# LoRa_SX1276_Shield_-_v1_1_0.net
KiCad netlist of a schematic drawn in EAGLE
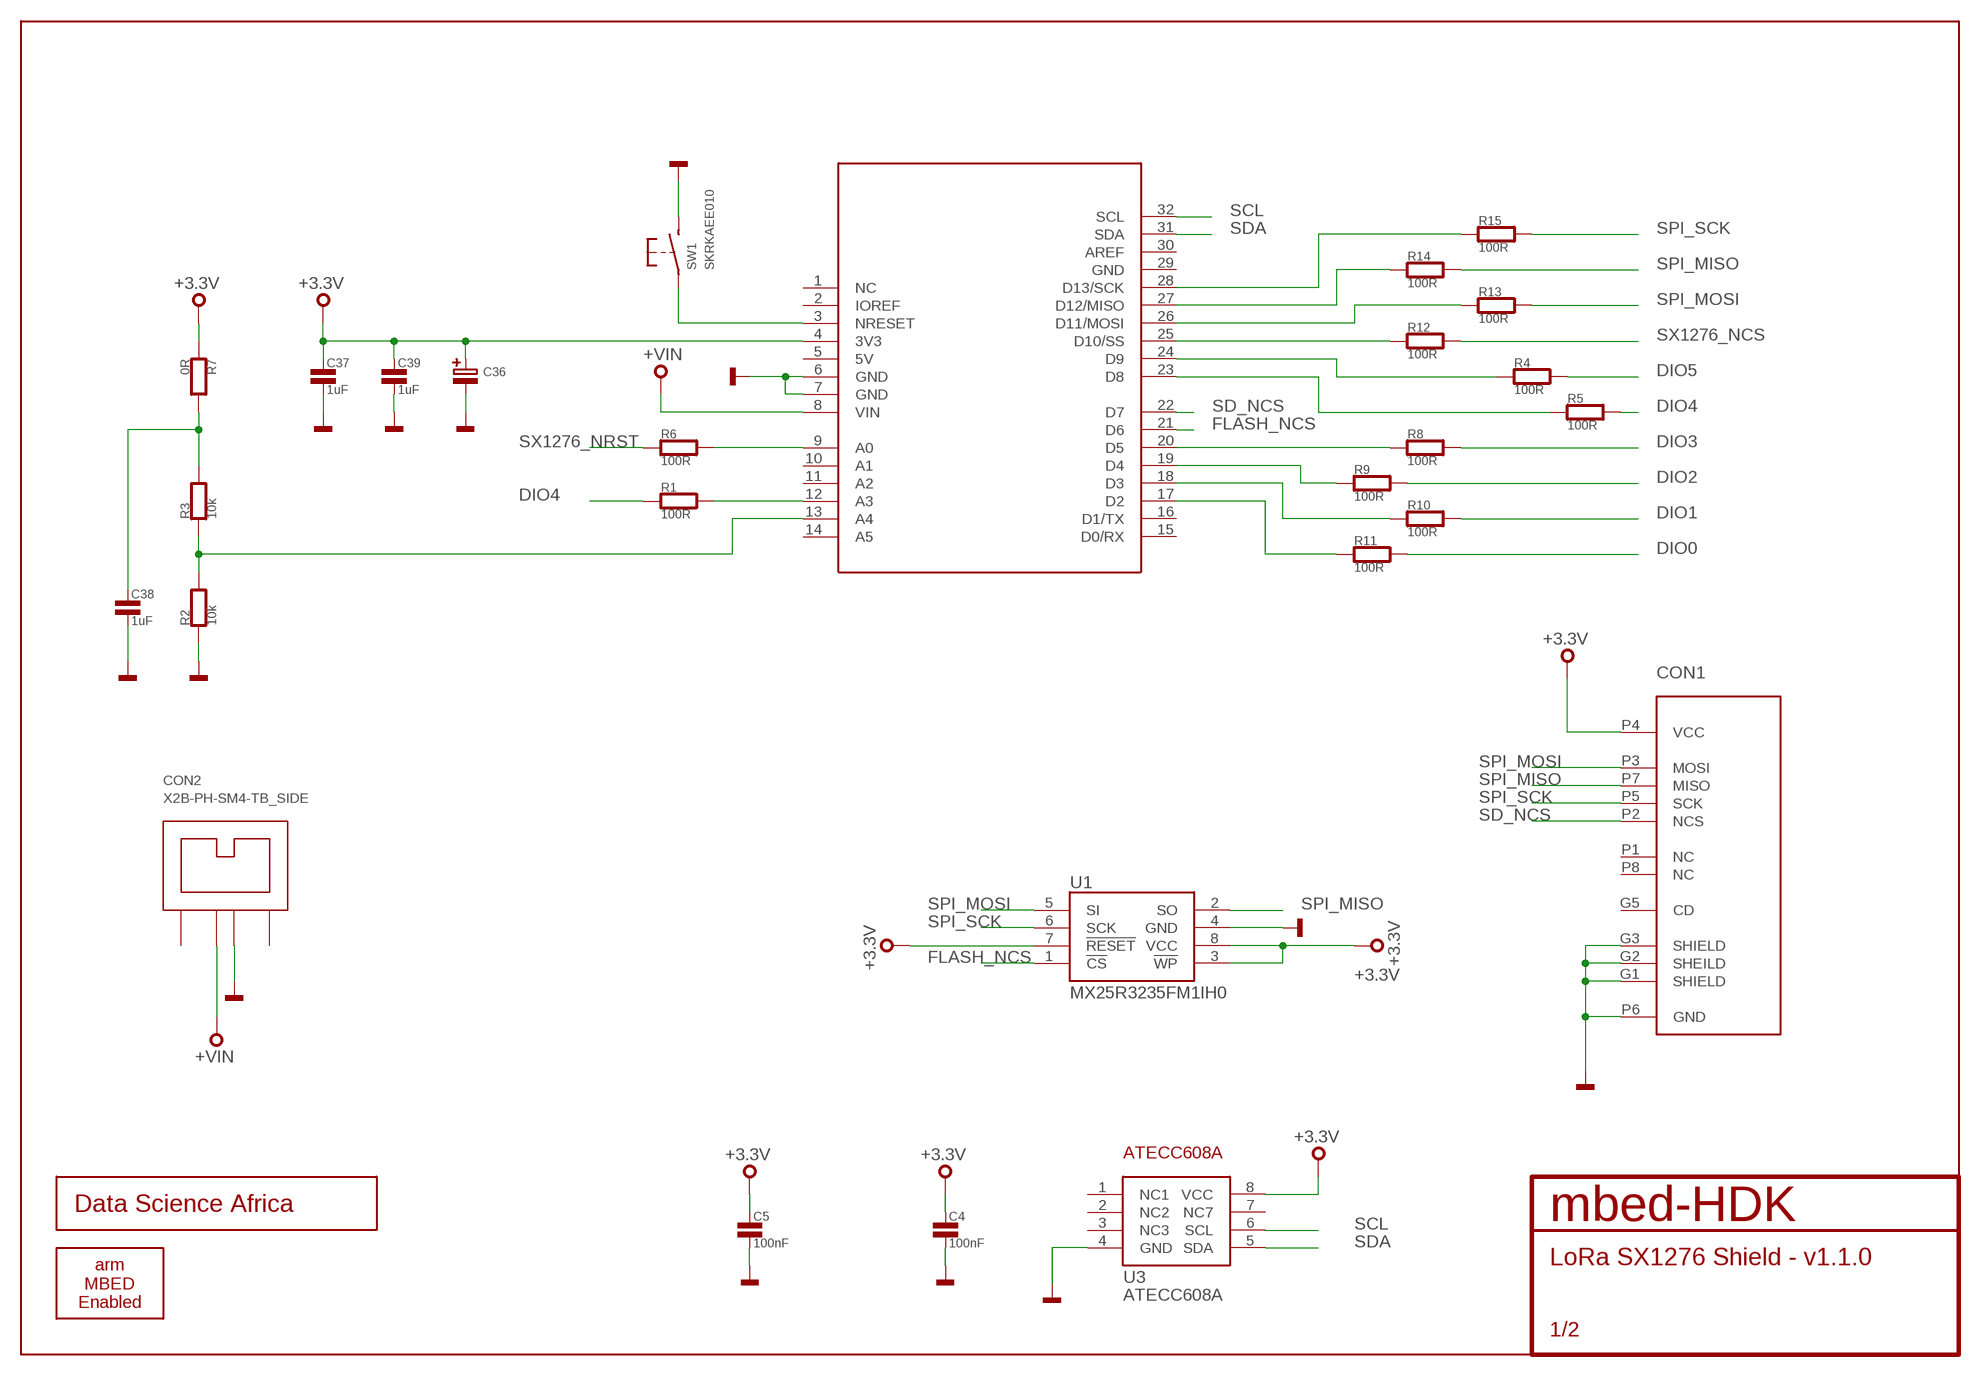
[diagram p0: schematic, sheet 1]
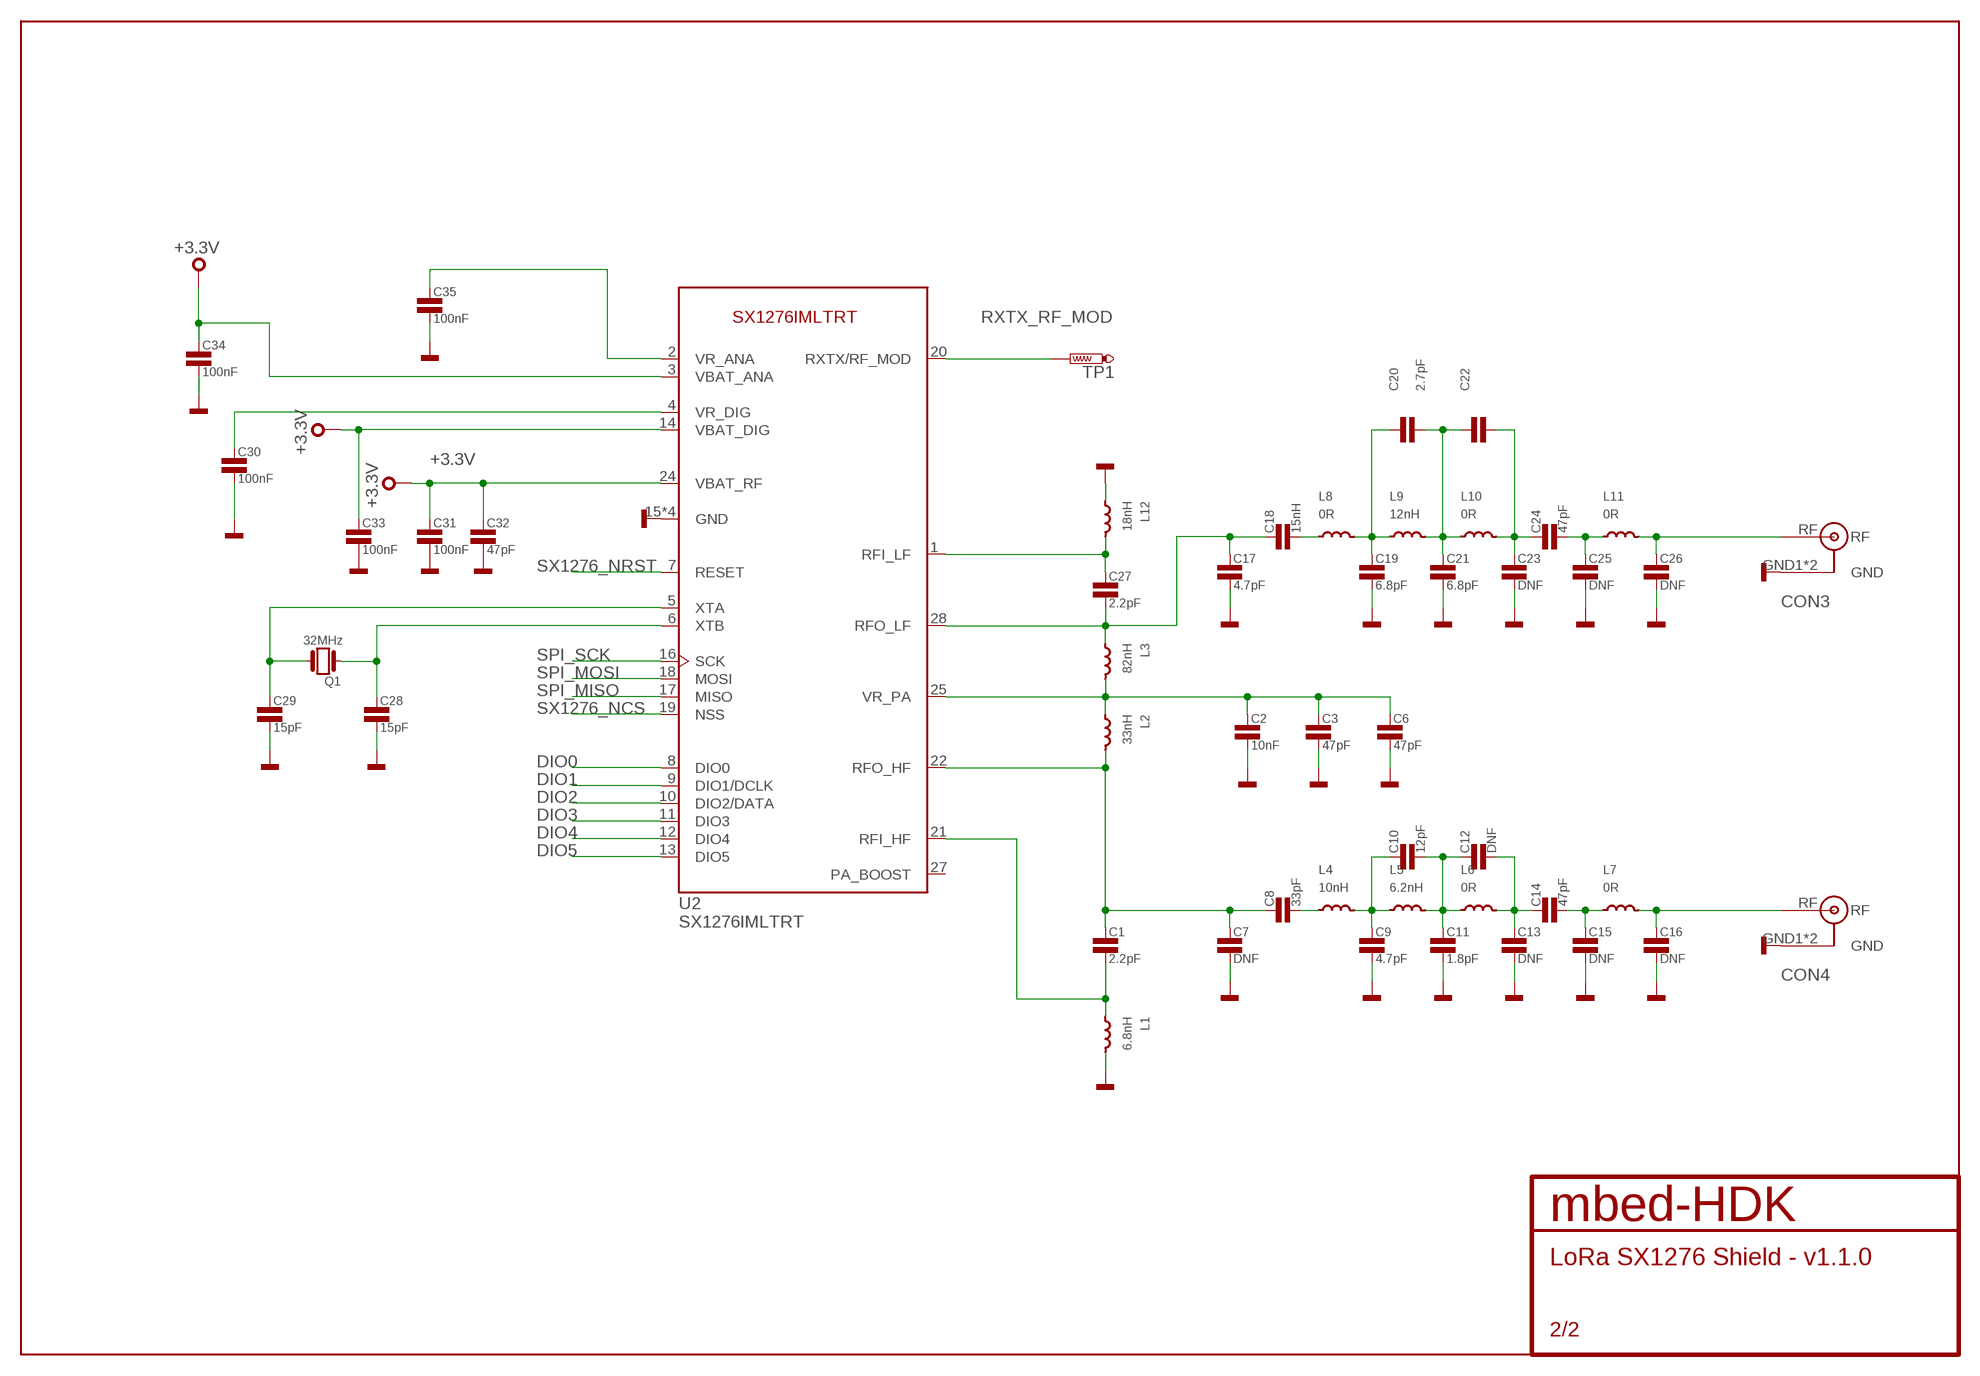
[diagram p1: schematic, sheet 2]

(export (version "E")
  (design (tool "Eeschema 10.0.6"))
  (components
    (comp (ref "C1")
      (value "2.2pF")
      (footprint "eagle-import:0402")
      (libsource (lib "eagle-import") (part "C0402"))
    )
    (comp (ref "C2")
      (value "10nF")
      (footprint "eagle-import:0402")
      (libsource (lib "eagle-import") (part "C0402"))
    )
    (comp (ref "C3")
      (value "47pF")
      (footprint "eagle-import:0402")
      (libsource (lib "eagle-import") (part "C0402"))
    )
    (comp (ref "C6")
      (value "47pF")
      (footprint "eagle-import:0402")
      (libsource (lib "eagle-import") (part "C0402"))
    )
    (comp (ref "C7")
      (value "DNF")
      (footprint "eagle-import:0402")
      (libsource (lib "eagle-import") (part "C0402"))
    )
    (comp (ref "C8")
      (value "33pF")
      (footprint "eagle-import:0402")
      (libsource (lib "eagle-import") (part "C0402"))
    )
    (comp (ref "C9")
      (value "4.7pF")
      (footprint "eagle-import:0402")
      (libsource (lib "eagle-import") (part "C0402"))
    )
    (comp (ref "C10")
      (value "12pF")
      (footprint "eagle-import:0402")
      (libsource (lib "eagle-import") (part "C0402"))
    )
    (comp (ref "C11")
      (value "1.8pF")
      (footprint "eagle-import:0402")
      (libsource (lib "eagle-import") (part "C0402"))
    )
    (comp (ref "C12")
      (value "DNF")
      (footprint "eagle-import:0402")
      (libsource (lib "eagle-import") (part "C0402"))
    )
    (comp (ref "C13")
      (value "DNF")
      (footprint "eagle-import:0402")
      (libsource (lib "eagle-import") (part "C0402"))
    )
    (comp (ref "C14")
      (value "47pF")
      (footprint "eagle-import:0402")
      (libsource (lib "eagle-import") (part "C0402"))
    )
    (comp (ref "C15")
      (value "DNF")
      (footprint "eagle-import:0402")
      (libsource (lib "eagle-import") (part "C0402"))
    )
    (comp (ref "C16")
      (value "DNF")
      (footprint "eagle-import:0402")
      (libsource (lib "eagle-import") (part "C0402"))
    )
    (comp (ref "C17")
      (value "4.7pF")
      (footprint "eagle-import:0402")
      (libsource (lib "eagle-import") (part "C0402"))
    )
    (comp (ref "C18")
      (value "15nH")
      (footprint "eagle-import:0402")
      (libsource (lib "eagle-import") (part "C0402"))
    )
    (comp (ref "C19")
      (value "6.8pF")
      (footprint "eagle-import:0402")
      (libsource (lib "eagle-import") (part "C0402"))
    )
    (comp (ref "C20")
      (value "2.7pF")
      (footprint "eagle-import:0402")
      (libsource (lib "eagle-import") (part "C0402"))
    )
    (comp (ref "C21")
      (value "6.8pF")
      (footprint "eagle-import:0402")
      (libsource (lib "eagle-import") (part "C0402"))
    )
    (comp (ref "C22")
      (value "C0402")
      (footprint "eagle-import:0402")
      (libsource (lib "eagle-import") (part "C0402"))
    )
    (comp (ref "C23")
      (value "DNF")
      (footprint "eagle-import:0402")
      (libsource (lib "eagle-import") (part "C0402"))
    )
    (comp (ref "C24")
      (value "47pF")
      (footprint "eagle-import:0402")
      (libsource (lib "eagle-import") (part "C0402"))
    )
    (comp (ref "C25")
      (value "DNF")
      (footprint "eagle-import:0402")
      (libsource (lib "eagle-import") (part "C0402"))
    )
    (comp (ref "C26")
      (value "DNF")
      (footprint "eagle-import:0402")
      (libsource (lib "eagle-import") (part "C0402"))
    )
    (comp (ref "C27")
      (value "2.2pF")
      (footprint "eagle-import:0402")
      (libsource (lib "eagle-import") (part "C0402"))
    )
    (comp (ref "C28")
      (value "15pF")
      (footprint "eagle-import:0402")
      (libsource (lib "eagle-import") (part "C0402"))
    )
    (comp (ref "C29")
      (value "15pF")
      (footprint "eagle-import:0402")
      (libsource (lib "eagle-import") (part "C0402"))
    )
    (comp (ref "C30")
      (value "100nF")
      (footprint "eagle-import:0402")
      (libsource (lib "eagle-import") (part "C0402"))
    )
    (comp (ref "C31")
      (value "100nF")
      (footprint "eagle-import:0402")
      (libsource (lib "eagle-import") (part "C0402"))
    )
    (comp (ref "C32")
      (value "47pF")
      (footprint "eagle-import:0402")
      (libsource (lib "eagle-import") (part "C0402"))
    )
    (comp (ref "C33")
      (value "100nF")
      (footprint "eagle-import:0402")
      (libsource (lib "eagle-import") (part "C0402"))
    )
    (comp (ref "C34")
      (value "100nF")
      (footprint "eagle-import:0402")
      (libsource (lib "eagle-import") (part "C0402"))
    )
    (comp (ref "C35")
      (value "100nF")
      (footprint "eagle-import:0402")
      (libsource (lib "eagle-import") (part "C0402"))
    )
    (comp (ref "CON3")
      (value "U.FL")
      (footprint "eagle-import:U.FL-R-SMT-1")
      (fields (field (name "MF") "Hirose"))
      (libsource (lib "eagle-import") (part "U.FL"))
    )
    (comp (ref "CON4")
      (value "U.FL")
      (footprint "eagle-import:U.FL-R-SMT-1")
      (fields (field (name "MF") "Hirose"))
      (libsource (lib "eagle-import") (part "U.FL"))
    )
    (comp (ref "L1")
      (value "6.8nH")
      (footprint "eagle-import:0402")
      (libsource (lib "eagle-import") (part "L0402"))
    )
    (comp (ref "L2")
      (value "33nH")
      (footprint "eagle-import:0402")
      (libsource (lib "eagle-import") (part "L0402"))
    )
    (comp (ref "L3")
      (value "82nH")
      (footprint "eagle-import:0402")
      (libsource (lib "eagle-import") (part "L0402"))
    )
    (comp (ref "L4")
      (value "10nH")
      (footprint "eagle-import:0402")
      (libsource (lib "eagle-import") (part "L0402"))
    )
    (comp (ref "L5")
      (value "6.2nH")
      (footprint "eagle-import:0402")
      (libsource (lib "eagle-import") (part "L0402"))
    )
    (comp (ref "L6")
      (value "0R")
      (footprint "eagle-import:0402")
      (libsource (lib "eagle-import") (part "L0402"))
    )
    (comp (ref "L7")
      (value "0R")
      (footprint "eagle-import:0402")
      (libsource (lib "eagle-import") (part "L0402"))
    )
    (comp (ref "L8")
      (value "0R")
      (footprint "eagle-import:0402")
      (libsource (lib "eagle-import") (part "L0402"))
    )
    (comp (ref "L9")
      (value "12nH")
      (footprint "eagle-import:0402")
      (libsource (lib "eagle-import") (part "L0402"))
    )
    (comp (ref "L10")
      (value "0R")
      (footprint "eagle-import:0402")
      (libsource (lib "eagle-import") (part "L0402"))
    )
    (comp (ref "L11")
      (value "0R")
      (footprint "eagle-import:0402")
      (libsource (lib "eagle-import") (part "L0402"))
    )
    (comp (ref "L12")
      (value "18nH")
      (footprint "eagle-import:0402")
      (libsource (lib "eagle-import") (part "L0402"))
    )
    (comp (ref "Q1")
      (value "32MHz")
      (footprint "eagle-import:3.2X.2.5")
      (libsource (lib "eagle-import") (part "GENERIC-CRYSTAL_3.2X2.5"))
    )
    (comp (ref "TP1")
      (value "PTR1TP12R")
      (footprint "eagle-import:TP12R")
      (libsource (lib "eagle-import") (part "PTR1TP12R"))
    )
    (comp (ref "U2")
      (value "SX1276IMLTRT")
      (footprint "eagle-import:QFN65P600X600X100-29N")
      (fields (field (name "MF") "Semtec"))
      (libsource (lib "eagle-import") (part "SX1276IMLTRT"))
    )
    (comp (ref "BRD2")
      (value "ARDUINO-R3_APPS")
      (footprint "eagle-import:ARDUINO-R3-APPS-SHEILD")
      (libsource (lib "eagle-import") (part "ARDUINO-R3_APPS"))
    )
    (comp (ref "C4")
      (value "100nF")
      (footprint "eagle-import:0402")
      (libsource (lib "eagle-import") (part "C0402"))
    )
    (comp (ref "C5")
      (value "100nF")
      (footprint "eagle-import:0402")
      (libsource (lib "eagle-import") (part "C0402"))
    )
    (comp (ref "C36")
      (value "C-POLB")
      (footprint "eagle-import:SMC_B")
      (fields (field (name "MF") "Kemet"))
      (libsource (lib "eagle-import") (part "C-POLB"))
    )
    (comp (ref "C37")
      (value "1uF")
      (footprint "eagle-import:0603")
      (libsource (lib "eagle-import") (part "C0603"))
    )
    (comp (ref "C38")
      (value "1uF")
      (footprint "eagle-import:0603")
      (libsource (lib "eagle-import") (part "C0603"))
    )
    (comp (ref "C39")
      (value "1uF")
      (footprint "eagle-import:0402")
      (libsource (lib "eagle-import") (part "C0402"))
    )
    (comp (ref "CON1")
      (value "MICRO-SDMOLEX-47571-0001")
      (footprint "eagle-import:MOLEX-47571-0001")
      (libsource (lib "eagle-import") (part "MICRO-SDMOLEX-47571-0001"))
    )
    (comp (ref "CON2")
      (value "X2B-PH-SM4-TB_SIDE")
      (footprint "eagle-import:S2B-PH-SM4-TB")
      (libsource (lib "eagle-import") (part "X2B-PH-SM4-TB_SIDE"))
    )
    (comp (ref "R1")
      (value "100R")
      (footprint "eagle-import:0402")
      (libsource (lib "eagle-import") (part "R0402"))
    )
    (comp (ref "R2")
      (value "10k")
      (footprint "eagle-import:0402")
      (libsource (lib "eagle-import") (part "R0402"))
    )
    (comp (ref "R3")
      (value "10k")
      (footprint "eagle-import:0402")
      (libsource (lib "eagle-import") (part "R0402"))
    )
    (comp (ref "R4")
      (value "100R")
      (footprint "eagle-import:0402")
      (libsource (lib "eagle-import") (part "R0402"))
    )
    (comp (ref "R5")
      (value "100R")
      (footprint "eagle-import:0402")
      (libsource (lib "eagle-import") (part "R0402"))
    )
    (comp (ref "R6")
      (value "100R")
      (footprint "eagle-import:0402")
      (libsource (lib "eagle-import") (part "R0402"))
    )
    (comp (ref "R7")
      (value "0R")
      (footprint "eagle-import:0402")
      (libsource (lib "eagle-import") (part "R0402"))
    )
    (comp (ref "R8")
      (value "100R")
      (footprint "eagle-import:0402")
      (libsource (lib "eagle-import") (part "R0402"))
    )
    (comp (ref "R9")
      (value "100R")
      (footprint "eagle-import:0402")
      (libsource (lib "eagle-import") (part "R0402"))
    )
    (comp (ref "R10")
      (value "100R")
      (footprint "eagle-import:0402")
      (libsource (lib "eagle-import") (part "R0402"))
    )
    (comp (ref "R11")
      (value "100R")
      (footprint "eagle-import:0402")
      (libsource (lib "eagle-import") (part "R0402"))
    )
    (comp (ref "R12")
      (value "100R")
      (footprint "eagle-import:0402")
      (libsource (lib "eagle-import") (part "R0402"))
    )
    (comp (ref "R13")
      (value "100R")
      (footprint "eagle-import:0402")
      (libsource (lib "eagle-import") (part "R0402"))
    )
    (comp (ref "R14")
      (value "100R")
      (footprint "eagle-import:0402")
      (libsource (lib "eagle-import") (part "R0402"))
    )
    (comp (ref "R15")
      (value "100R")
      (footprint "eagle-import:0402")
      (libsource (lib "eagle-import") (part "R0402"))
    )
    (comp (ref "SS1")
      (value "ARM-MBED-ENABLED-12MM")
      (footprint "eagle-import:ARM-MBED-ENABLED-12MM")
      (libsource (lib "eagle-import") (part "ARM-MBED-ENABLED-12MM"))
    )
    (comp (ref "SS2")
      (value "DATA-SCIENCE-AFRICA")
      (footprint "eagle-import:DATA-SCIENCE-AFRICA")
      (libsource (lib "eagle-import") (part "DATA-SCIENCE-AFRICA"))
    )
    (comp (ref "SW1")
      (value "SKRKAEE010")
      (footprint "eagle-import:SKRKAEE010")
      (fields (field (name "MF") "ALPS"))
      (libsource (lib "eagle-import") (part "SKRKAEE010"))
    )
    (comp (ref "U1")
      (value "MX25R3235FM1IH0")
      (footprint "eagle-import:SO8")
      (fields (field (name "MF") "Macronix"))
      (libsource (lib "eagle-import") (part "MX25R3235FM1IH0"))
    )
    (comp (ref "U3")
      (value "ATECC608A")
      (footprint "eagle-import:SO8")
      (libsource (lib "eagle-import") (part "ATECC608A"))
    )
  )
  (nets
    (net (code "1") (name "+3.3V") (class "Default")
      (node (ref "BRD2") (pin "4") (pinfunction "3V3_4") (pintype "bidirectional"))
      (node (ref "C31") (pin "1") (pinfunction "P$1_1") (pintype "passive"))
      (node (ref "C32") (pin "1") (pinfunction "P$1_1") (pintype "passive"))
      (node (ref "C33") (pin "1") (pinfunction "P$1_1") (pintype "passive"))
      (node (ref "C34") (pin "1") (pinfunction "P$1_1") (pintype "passive"))
      (node (ref "C36") (pin "+") (pinfunction "+_+") (pintype "passive"))
      (node (ref "C37") (pin "1") (pinfunction "P$1_1") (pintype "passive"))
      (node (ref "C39") (pin "1") (pinfunction "P$1_1") (pintype "passive"))
      (node (ref "C4") (pin "1") (pinfunction "P$1_1") (pintype "passive"))
      (node (ref "C5") (pin "1") (pinfunction "P$1_1") (pintype "passive"))
      (node (ref "CON1") (pin "P4") (pinfunction "VCC_P4") (pintype "bidirectional"))
      (node (ref "R7") (pin "1") (pinfunction "P$1_1") (pintype "passive"))
      (node (ref "U1") (pin "3") (pinfunction "~{WP}_3") (pintype "bidirectional"))
      (node (ref "U1") (pin "7") (pinfunction "~{RESET}_7") (pintype "bidirectional"))
      (node (ref "U1") (pin "8") (pinfunction "VCC_8") (pintype "bidirectional"))
      (node (ref "U2") (pin "14") (pinfunction "VBAT_DIG_14") (pintype "power_in"))
      (node (ref "U2") (pin "24") (pinfunction "VBAT_RF_24") (pintype "output"))
      (node (ref "U2") (pin "3") (pinfunction "VBAT_ANA_3") (pintype "power_in"))
      (node (ref "U3") (pin "8") (pinfunction "VCC_8") (pintype "bidirectional"))
    )
    (net (code "2") (name "+VIN") (class "Default")
      (node (ref "BRD2") (pin "8") (pinfunction "VIN_8") (pintype "bidirectional"))
      (node (ref "CON2") (pin "P$1") (pinfunction "P$1_P$1") (pintype "bidirectional"))
    )
    (net (code "3") (name "DIO0") (class "Default")
      (node (ref "R11") (pin "2") (pinfunction "P$2_2") (pintype "passive"))
      (node (ref "U2") (pin "8") (pinfunction "DIO0_8") (pintype "bidirectional"))
    )
    (net (code "4") (name "DIO1") (class "Default")
      (node (ref "R10") (pin "2") (pinfunction "P$2_2") (pintype "passive"))
      (node (ref "U2") (pin "9") (pinfunction "DIO1/DCLK_9") (pintype "bidirectional"))
    )
    (net (code "5") (name "DIO2") (class "Default")
      (node (ref "R9") (pin "2") (pinfunction "P$2_2") (pintype "passive"))
      (node (ref "U2") (pin "10") (pinfunction "DIO2/DATA_10") (pintype "bidirectional"))
    )
    (net (code "6") (name "DIO3") (class "Default")
      (node (ref "R8") (pin "2") (pinfunction "P$2_2") (pintype "passive"))
      (node (ref "U2") (pin "11") (pinfunction "DIO3_11") (pintype "bidirectional"))
    )
    (net (code "7") (name "DIO4") (class "Default")
      (node (ref "R1") (pin "1") (pinfunction "P$1_1") (pintype "passive"))
      (node (ref "R5") (pin "2") (pinfunction "P$2_2") (pintype "passive"))
      (node (ref "U2") (pin "12") (pinfunction "DIO4_12") (pintype "bidirectional"))
    )
    (net (code "8") (name "DIO5") (class "Default")
      (node (ref "R4") (pin "2") (pinfunction "P$2_2") (pintype "passive"))
      (node (ref "U2") (pin "13") (pinfunction "DIO5_13") (pintype "bidirectional"))
    )
    (net (code "9") (name "FLASH_NCS") (class "Default")
      (node (ref "BRD2") (pin "21") (pinfunction "D6_21") (pintype "bidirectional"))
      (node (ref "U1") (pin "1") (pinfunction "~{CS}_1") (pintype "bidirectional"))
    )
    (net (code "10") (name "GND") (class "Default")
      (node (ref "BRD2") (pin "6") (pinfunction "GND_6") (pintype "bidirectional"))
      (node (ref "BRD2") (pin "7") (pinfunction "GND_7") (pintype "bidirectional"))
      (node (ref "C11") (pin "2") (pinfunction "P$2_2") (pintype "passive"))
      (node (ref "C13") (pin "2") (pinfunction "P$2_2") (pintype "passive"))
      (node (ref "C15") (pin "2") (pinfunction "P$2_2") (pintype "passive"))
      (node (ref "C16") (pin "2") (pinfunction "P$2_2") (pintype "passive"))
      (node (ref "C17") (pin "2") (pinfunction "P$2_2") (pintype "passive"))
      (node (ref "C19") (pin "2") (pinfunction "P$2_2") (pintype "passive"))
      (node (ref "C2") (pin "2") (pinfunction "P$2_2") (pintype "passive"))
      (node (ref "C21") (pin "2") (pinfunction "P$2_2") (pintype "passive"))
      (node (ref "C23") (pin "2") (pinfunction "P$2_2") (pintype "passive"))
      (node (ref "C25") (pin "2") (pinfunction "P$2_2") (pintype "passive"))
      (node (ref "C26") (pin "2") (pinfunction "P$2_2") (pintype "passive"))
      (node (ref "C28") (pin "2") (pinfunction "P$2_2") (pintype "passive"))
      (node (ref "C29") (pin "2") (pinfunction "P$2_2") (pintype "passive"))
      (node (ref "C3") (pin "2") (pinfunction "P$2_2") (pintype "passive"))
      (node (ref "C30") (pin "2") (pinfunction "P$2_2") (pintype "passive"))
      (node (ref "C31") (pin "2") (pinfunction "P$2_2") (pintype "passive"))
      (node (ref "C32") (pin "2") (pinfunction "P$2_2") (pintype "passive"))
      (node (ref "C33") (pin "2") (pinfunction "P$2_2") (pintype "passive"))
      (node (ref "C34") (pin "2") (pinfunction "P$2_2") (pintype "passive"))
      (node (ref "C35") (pin "2") (pinfunction "P$2_2") (pintype "passive"))
      (node (ref "C36") (pin "-") (pinfunction "-_-") (pintype "passive"))
      (node (ref "C37") (pin "2") (pinfunction "P$2_2") (pintype "passive"))
      (node (ref "C38") (pin "2") (pinfunction "P$2_2") (pintype "passive"))
      (node (ref "C39") (pin "2") (pinfunction "P$2_2") (pintype "passive"))
      (node (ref "C4") (pin "2") (pinfunction "P$2_2") (pintype "passive"))
      (node (ref "C5") (pin "2") (pinfunction "P$2_2") (pintype "passive"))
      (node (ref "C6") (pin "2") (pinfunction "P$2_2") (pintype "passive"))
      (node (ref "C7") (pin "2") (pinfunction "P$2_2") (pintype "passive"))
      (node (ref "C9") (pin "2") (pinfunction "P$2_2") (pintype "passive"))
      (node (ref "CON1") (pin "G1") (pinfunction "SHIELD_G1") (pintype "bidirectional"))
      (node (ref "CON1") (pin "G2") (pinfunction "SHEILD_G2") (pintype "bidirectional"))
      (node (ref "CON1") (pin "G3") (pinfunction "SHIELD_G3") (pintype "bidirectional"))
      (node (ref "CON1") (pin "P6") (pinfunction "GND_P6") (pintype "bidirectional"))
      (node (ref "CON2") (pin "P$2") (pinfunction "P$2_P$2") (pintype "bidirectional"))
      (node (ref "CON3") (pin "GND1") (pinfunction "GND_GND1") (pintype "bidirectional"))
      (node (ref "CON3") (pin "GND2") (pinfunction "GND_GND2") (pintype "bidirectional"))
      (node (ref "CON4") (pin "GND1") (pinfunction "GND_GND1") (pintype "bidirectional"))
      (node (ref "CON4") (pin "GND2") (pinfunction "GND_GND2") (pintype "bidirectional"))
      (node (ref "L1") (pin "2") (pinfunction "P$2_2") (pintype "bidirectional"))
      (node (ref "L12") (pin "1") (pinfunction "P$1_1") (pintype "bidirectional"))
      (node (ref "R2") (pin "1") (pinfunction "P$1_1") (pintype "passive"))
      (node (ref "SW1") (pin "P$2") (pinfunction "S_P$2") (pintype "passive"))
      (node (ref "U1") (pin "4") (pinfunction "GND_4") (pintype "bidirectional"))
      (node (ref "U2") (pin "15") (pinfunction "GND_15") (pintype "power_in"))
      (node (ref "U2") (pin "23") (pinfunction "GND_23") (pintype "power_in"))
      (node (ref "U2") (pin "26") (pinfunction "GND_26") (pintype "power_in"))
      (node (ref "U2") (pin "29") (pinfunction "GND_29") (pintype "power_in"))
      (node (ref "U3") (pin "4") (pinfunction "GND_4") (pintype "bidirectional"))
    )
    (net (code "11") (name "Net-(BRD2-A0)") (class "Default")
      (node (ref "BRD2") (pin "9") (pinfunction "A0_9") (pintype "bidirectional"))
      (node (ref "R6") (pin "2") (pinfunction "P$2_2") (pintype "passive"))
    )
    (net (code "12") (name "Net-(BRD2-A3)") (class "Default")
      (node (ref "BRD2") (pin "12") (pinfunction "A3_12") (pintype "bidirectional"))
      (node (ref "R1") (pin "2") (pinfunction "P$2_2") (pintype "passive"))
    )
    (net (code "13") (name "Net-(BRD2-A4)") (class "Default")
      (node (ref "BRD2") (pin "13") (pinfunction "A4_13") (pintype "bidirectional"))
      (node (ref "R2") (pin "2") (pinfunction "P$2_2") (pintype "passive"))
      (node (ref "R3") (pin "1") (pinfunction "P$1_1") (pintype "passive"))
    )
    (net (code "14") (name "Net-(BRD2-D2)") (class "Default")
      (node (ref "BRD2") (pin "17") (pinfunction "D2_17") (pintype "bidirectional"))
      (node (ref "R11") (pin "1") (pinfunction "P$1_1") (pintype "passive"))
    )
    (net (code "15") (name "Net-(BRD2-D3)") (class "Default")
      (node (ref "BRD2") (pin "18") (pinfunction "D3_18") (pintype "bidirectional"))
      (node (ref "R10") (pin "1") (pinfunction "P$1_1") (pintype "passive"))
    )
    (net (code "16") (name "Net-(BRD2-D4)") (class "Default")
      (node (ref "BRD2") (pin "19") (pinfunction "D4_19") (pintype "bidirectional"))
      (node (ref "R9") (pin "1") (pinfunction "P$1_1") (pintype "passive"))
    )
    (net (code "17") (name "Net-(BRD2-D5)") (class "Default")
      (node (ref "BRD2") (pin "20") (pinfunction "D5_20") (pintype "bidirectional"))
      (node (ref "R8") (pin "1") (pinfunction "P$1_1") (pintype "passive"))
    )
    (net (code "18") (name "Net-(BRD2-D8)") (class "Default")
      (node (ref "BRD2") (pin "23") (pinfunction "D8_23") (pintype "bidirectional"))
      (node (ref "R5") (pin "1") (pinfunction "P$1_1") (pintype "passive"))
    )
    (net (code "19") (name "Net-(BRD2-D9)") (class "Default")
      (node (ref "BRD2") (pin "24") (pinfunction "D9_24") (pintype "bidirectional"))
      (node (ref "R4") (pin "1") (pinfunction "P$1_1") (pintype "passive"))
    )
    (net (code "20") (name "Net-(BRD2-D10{slash}SS)") (class "Default")
      (node (ref "BRD2") (pin "25") (pinfunction "D10/SS_25") (pintype "bidirectional"))
      (node (ref "R12") (pin "1") (pinfunction "P$1_1") (pintype "passive"))
    )
    (net (code "21") (name "Net-(BRD2-D11{slash}MOSI)") (class "Default")
      (node (ref "BRD2") (pin "26") (pinfunction "D11/MOSI_26") (pintype "bidirectional"))
      (node (ref "R13") (pin "1") (pinfunction "P$1_1") (pintype "passive"))
    )
    (net (code "22") (name "Net-(BRD2-D12{slash}MISO)") (class "Default")
      (node (ref "BRD2") (pin "27") (pinfunction "D12/MISO_27") (pintype "bidirectional"))
      (node (ref "R14") (pin "1") (pinfunction "P$1_1") (pintype "passive"))
    )
    (net (code "23") (name "Net-(BRD2-D13{slash}SCK)") (class "Default")
      (node (ref "BRD2") (pin "28") (pinfunction "D13/SCK_28") (pintype "bidirectional"))
      (node (ref "R15") (pin "1") (pinfunction "P$1_1") (pintype "passive"))
    )
    (net (code "24") (name "Net-(BRD2-NRESET)") (class "Default")
      (node (ref "BRD2") (pin "3") (pinfunction "NRESET_3") (pintype "bidirectional"))
      (node (ref "SW1") (pin "P$1") (pinfunction "P_P$1") (pintype "passive"))
    )
    (net (code "25") (name "Net-(C1-P$1)") (class "Default")
      (node (ref "C1") (pin "1") (pinfunction "P$1_1") (pintype "passive"))
      (node (ref "C7") (pin "1") (pinfunction "P$1_1") (pintype "passive"))
      (node (ref "C8") (pin "1") (pinfunction "P$1_1") (pintype "passive"))
      (node (ref "L2") (pin "2") (pinfunction "P$2_2") (pintype "bidirectional"))
      (node (ref "U2") (pin "22") (pinfunction "RFO_HF_22") (pintype "output"))
    )
    (net (code "26") (name "Net-(C1-P$2)") (class "Default")
      (node (ref "C1") (pin "2") (pinfunction "P$2_2") (pintype "passive"))
      (node (ref "L1") (pin "1") (pinfunction "P$1_1") (pintype "bidirectional"))
      (node (ref "U2") (pin "21") (pinfunction "RFI_HF_21") (pintype "input"))
    )
    (net (code "27") (name "Net-(C2-P$1)") (class "Default")
      (node (ref "C2") (pin "1") (pinfunction "P$1_1") (pintype "passive"))
      (node (ref "C3") (pin "1") (pinfunction "P$1_1") (pintype "passive"))
      (node (ref "C6") (pin "1") (pinfunction "P$1_1") (pintype "passive"))
      (node (ref "L2") (pin "1") (pinfunction "P$1_1") (pintype "bidirectional"))
      (node (ref "L3") (pin "2") (pinfunction "P$2_2") (pintype "bidirectional"))
      (node (ref "U2") (pin "25") (pinfunction "VR_PA_25") (pintype "output"))
    )
    (net (code "28") (name "Net-(C8-P$2)") (class "Default")
      (node (ref "C8") (pin "2") (pinfunction "P$2_2") (pintype "passive"))
      (node (ref "L4") (pin "1") (pinfunction "P$1_1") (pintype "bidirectional"))
    )
    (net (code "29") (name "Net-(C10-P$1)") (class "Default")
      (node (ref "C10") (pin "1") (pinfunction "P$1_1") (pintype "passive"))
      (node (ref "C9") (pin "1") (pinfunction "P$1_1") (pintype "passive"))
      (node (ref "L4") (pin "2") (pinfunction "P$2_2") (pintype "bidirectional"))
      (node (ref "L5") (pin "1") (pinfunction "P$1_1") (pintype "bidirectional"))
    )
    (net (code "30") (name "Net-(C10-P$2)") (class "Default")
      (node (ref "C10") (pin "2") (pinfunction "P$2_2") (pintype "passive"))
      (node (ref "C11") (pin "1") (pinfunction "P$1_1") (pintype "passive"))
      (node (ref "C12") (pin "1") (pinfunction "P$1_1") (pintype "passive"))
      (node (ref "L5") (pin "2") (pinfunction "P$2_2") (pintype "bidirectional"))
      (node (ref "L6") (pin "1") (pinfunction "P$1_1") (pintype "bidirectional"))
    )
    (net (code "31") (name "Net-(C12-P$2)") (class "Default")
      (node (ref "C12") (pin "2") (pinfunction "P$2_2") (pintype "passive"))
      (node (ref "C13") (pin "1") (pinfunction "P$1_1") (pintype "passive"))
      (node (ref "C14") (pin "1") (pinfunction "P$1_1") (pintype "passive"))
      (node (ref "L6") (pin "2") (pinfunction "P$2_2") (pintype "bidirectional"))
    )
    (net (code "32") (name "Net-(C14-P$2)") (class "Default")
      (node (ref "C14") (pin "2") (pinfunction "P$2_2") (pintype "passive"))
      (node (ref "C15") (pin "1") (pinfunction "P$1_1") (pintype "passive"))
      (node (ref "L7") (pin "1") (pinfunction "P$1_1") (pintype "bidirectional"))
    )
    (net (code "33") (name "Net-(C16-P$1)") (class "Default")
      (node (ref "C16") (pin "1") (pinfunction "P$1_1") (pintype "passive"))
      (node (ref "CON4") (pin "RF") (pinfunction "RF_RF") (pintype "bidirectional"))
      (node (ref "L7") (pin "2") (pinfunction "P$2_2") (pintype "bidirectional"))
    )
    (net (code "34") (name "Net-(C17-P$1)") (class "Default")
      (node (ref "C17") (pin "1") (pinfunction "P$1_1") (pintype "passive"))
      (node (ref "C18") (pin "1") (pinfunction "P$1_1") (pintype "passive"))
      (node (ref "C27") (pin "2") (pinfunction "P$2_2") (pintype "passive"))
      (node (ref "L3") (pin "1") (pinfunction "P$1_1") (pintype "bidirectional"))
      (node (ref "U2") (pin "28") (pinfunction "RFO_LF_28") (pintype "output"))
    )
    (net (code "35") (name "Net-(C18-P$2)") (class "Default")
      (node (ref "C18") (pin "2") (pinfunction "P$2_2") (pintype "passive"))
      (node (ref "L8") (pin "1") (pinfunction "P$1_1") (pintype "bidirectional"))
    )
    (net (code "36") (name "Net-(C19-P$1)") (class "Default")
      (node (ref "C19") (pin "1") (pinfunction "P$1_1") (pintype "passive"))
      (node (ref "C20") (pin "1") (pinfunction "P$1_1") (pintype "passive"))
      (node (ref "L8") (pin "2") (pinfunction "P$2_2") (pintype "bidirectional"))
      (node (ref "L9") (pin "1") (pinfunction "P$1_1") (pintype "bidirectional"))
    )
    (net (code "37") (name "Net-(C20-P$2)") (class "Default")
      (node (ref "C20") (pin "2") (pinfunction "P$2_2") (pintype "passive"))
      (node (ref "C21") (pin "1") (pinfunction "P$1_1") (pintype "passive"))
      (node (ref "C22") (pin "1") (pinfunction "P$1_1") (pintype "passive"))
      (node (ref "L10") (pin "1") (pinfunction "P$1_1") (pintype "bidirectional"))
      (node (ref "L9") (pin "2") (pinfunction "P$2_2") (pintype "bidirectional"))
    )
    (net (code "38") (name "Net-(C22-P$2)") (class "Default")
      (node (ref "C22") (pin "2") (pinfunction "P$2_2") (pintype "passive"))
      (node (ref "C23") (pin "1") (pinfunction "P$1_1") (pintype "passive"))
      (node (ref "C24") (pin "1") (pinfunction "P$1_1") (pintype "passive"))
      (node (ref "L10") (pin "2") (pinfunction "P$2_2") (pintype "bidirectional"))
    )
    (net (code "39") (name "Net-(C24-P$2)") (class "Default")
      (node (ref "C24") (pin "2") (pinfunction "P$2_2") (pintype "passive"))
      (node (ref "C25") (pin "1") (pinfunction "P$1_1") (pintype "passive"))
      (node (ref "L11") (pin "1") (pinfunction "P$1_1") (pintype "bidirectional"))
    )
    (net (code "40") (name "Net-(C26-P$1)") (class "Default")
      (node (ref "C26") (pin "1") (pinfunction "P$1_1") (pintype "passive"))
      (node (ref "CON3") (pin "RF") (pinfunction "RF_RF") (pintype "bidirectional"))
      (node (ref "L11") (pin "2") (pinfunction "P$2_2") (pintype "bidirectional"))
    )
    (net (code "41") (name "Net-(C27-P$1)") (class "Default")
      (node (ref "C27") (pin "1") (pinfunction "P$1_1") (pintype "passive"))
      (node (ref "L12") (pin "2") (pinfunction "P$2_2") (pintype "bidirectional"))
      (node (ref "U2") (pin "1") (pinfunction "RFI_LF_1") (pintype "input"))
    )
    (net (code "42") (name "Net-(C28-P$1)") (class "Default")
      (node (ref "C28") (pin "1") (pinfunction "P$1_1") (pintype "passive"))
      (node (ref "Q1") (pin "P$1") (pinfunction "1_P$1") (pintype "passive"))
      (node (ref "U2") (pin "6") (pinfunction "XTB_6") (pintype "bidirectional"))
    )
    (net (code "43") (name "Net-(C29-P$1)") (class "Default")
      (node (ref "C29") (pin "1") (pinfunction "P$1_1") (pintype "passive"))
      (node (ref "Q1") (pin "P$3") (pinfunction "2_P$3") (pintype "passive"))
      (node (ref "U2") (pin "5") (pinfunction "XTA_5") (pintype "bidirectional"))
    )
    (net (code "44") (name "Net-(C30-P$1)") (class "Default")
      (node (ref "C30") (pin "1") (pinfunction "P$1_1") (pintype "passive"))
      (node (ref "U2") (pin "4") (pinfunction "VR_DIG_4") (pintype "power_in"))
    )
    (net (code "45") (name "Net-(C35-P$1)") (class "Default")
      (node (ref "C35") (pin "1") (pinfunction "P$1_1") (pintype "passive"))
      (node (ref "U2") (pin "2") (pinfunction "VR_ANA_2") (pintype "power_in"))
    )
    (net (code "46") (name "Net-(C38-P$1)") (class "Default")
      (node (ref "C38") (pin "1") (pinfunction "P$1_1") (pintype "passive"))
      (node (ref "R3") (pin "2") (pinfunction "P$2_2") (pintype "passive"))
      (node (ref "R7") (pin "2") (pinfunction "P$2_2") (pintype "passive"))
    )
    (net (code "47") (name "RXTX_RF_MOD") (class "Default")
      (node (ref "TP1") (pin "TP") (pinfunction "TP_TP") (pintype "input"))
      (node (ref "U2") (pin "20") (pinfunction "RXTX/RF_MOD_20") (pintype "output"))
    )
    (net (code "48") (name "SCL") (class "Default")
      (node (ref "BRD2") (pin "32") (pinfunction "SCL_32") (pintype "bidirectional"))
      (node (ref "U3") (pin "6") (pinfunction "SCL_6") (pintype "bidirectional"))
    )
    (net (code "49") (name "SDA") (class "Default")
      (node (ref "BRD2") (pin "31") (pinfunction "SDA_31") (pintype "bidirectional"))
      (node (ref "U3") (pin "5") (pinfunction "SDA_5") (pintype "bidirectional"))
    )
    (net (code "50") (name "SD_NCS") (class "Default")
      (node (ref "BRD2") (pin "22") (pinfunction "D7_22") (pintype "bidirectional"))
      (node (ref "CON1") (pin "P2") (pinfunction "NCS_P2") (pintype "bidirectional"))
    )
    (net (code "51") (name "SPI_MISO") (class "Default")
      (node (ref "CON1") (pin "P7") (pinfunction "MISO_P7") (pintype "bidirectional"))
      (node (ref "R14") (pin "2") (pinfunction "P$2_2") (pintype "passive"))
      (node (ref "U1") (pin "2") (pinfunction "SO_2") (pintype "bidirectional"))
      (node (ref "U2") (pin "17") (pinfunction "MISO_17") (pintype "output"))
    )
    (net (code "52") (name "SPI_MOSI") (class "Default")
      (node (ref "CON1") (pin "P3") (pinfunction "MOSI_P3") (pintype "bidirectional"))
      (node (ref "R13") (pin "2") (pinfunction "P$2_2") (pintype "passive"))
      (node (ref "U1") (pin "5") (pinfunction "SI_5") (pintype "bidirectional"))
      (node (ref "U2") (pin "18") (pinfunction "MOSI_18") (pintype "input"))
    )
    (net (code "53") (name "SPI_SCK") (class "Default")
      (node (ref "CON1") (pin "P5") (pinfunction "SCK_P5") (pintype "bidirectional"))
      (node (ref "R15") (pin "2") (pinfunction "P$2_2") (pintype "passive"))
      (node (ref "U1") (pin "6") (pinfunction "SCK_6") (pintype "bidirectional"))
      (node (ref "U2") (pin "16") (pinfunction "SCK_16") (pintype "input"))
    )
    (net (code "54") (name "SX1276_NCS") (class "Default")
      (node (ref "R12") (pin "2") (pinfunction "P$2_2") (pintype "passive"))
      (node (ref "U2") (pin "19") (pinfunction "NSS_19") (pintype "input"))
    )
    (net (code "55") (name "SX1276_NRST") (class "Default")
      (node (ref "R6") (pin "1") (pinfunction "P$1_1") (pintype "passive"))
      (node (ref "U2") (pin "7") (pinfunction "RESET_7") (pintype "bidirectional"))
    )
    (net (code "56") (name "unconnected-(BRD2-5V-Pad5)") (class "Default")
      (node (ref "BRD2") (pin "5") (pinfunction "5V_5") (pintype "bidirectional"))
    )
    (net (code "57") (name "unconnected-(BRD2-A1-Pad10)") (class "Default")
      (node (ref "BRD2") (pin "10") (pinfunction "A1_10") (pintype "bidirectional"))
    )
    (net (code "58") (name "unconnected-(BRD2-A2-Pad11)") (class "Default")
      (node (ref "BRD2") (pin "11") (pinfunction "A2_11") (pintype "bidirectional"))
    )
    (net (code "59") (name "unconnected-(BRD2-A5-Pad14)") (class "Default")
      (node (ref "BRD2") (pin "14") (pinfunction "A5_14") (pintype "bidirectional"))
    )
    (net (code "60") (name "unconnected-(BRD2-AREF-Pad30)") (class "Default")
      (node (ref "BRD2") (pin "30") (pinfunction "AREF_30") (pintype "bidirectional"))
    )
    (net (code "61") (name "unconnected-(BRD2-D0{slash}RX-Pad15)") (class "Default")
      (node (ref "BRD2") (pin "15") (pinfunction "D0/RX_15") (pintype "bidirectional"))
    )
    (net (code "62") (name "unconnected-(BRD2-D1{slash}TX-Pad16)") (class "Default")
      (node (ref "BRD2") (pin "16") (pinfunction "D1/TX_16") (pintype "bidirectional"))
    )
    (net (code "63") (name "unconnected-(BRD2-GND-Pad29)") (class "Default")
      (node (ref "BRD2") (pin "29") (pinfunction "GND_29") (pintype "bidirectional"))
    )
    (net (code "64") (name "unconnected-(BRD2-IOREF-Pad2)") (class "Default")
      (node (ref "BRD2") (pin "2") (pinfunction "IOREF_2") (pintype "bidirectional"))
    )
    (net (code "65") (name "unconnected-(BRD2-NC-Pad1)") (class "Default")
      (node (ref "BRD2") (pin "1") (pinfunction "NC_1") (pintype "bidirectional"))
    )
    (net (code "66") (name "unconnected-(CON1-CD-PadG5)") (class "Default")
      (node (ref "CON1") (pin "G5") (pinfunction "CD_G5") (pintype "bidirectional"))
    )
    (net (code "67") (name "unconnected-(CON1-NC-PadP1)") (class "Default")
      (node (ref "CON1") (pin "P1") (pinfunction "NC_P1") (pintype "bidirectional"))
    )
    (net (code "68") (name "unconnected-(CON1-NC-PadP8)") (class "Default")
      (node (ref "CON1") (pin "P8") (pinfunction "NC_P8") (pintype "bidirectional"))
    )
    (net (code "69") (name "unconnected-(CON2-PadG1)") (class "Default")
      (node (ref "CON2") (pin "G1") (pinfunction "G1_G1") (pintype "bidirectional"))
    )
    (net (code "70") (name "unconnected-(CON2-PadG2)") (class "Default")
      (node (ref "CON2") (pin "G2") (pinfunction "G2_G2") (pintype "bidirectional"))
    )
    (net (code "71") (name "unconnected-(U2-PA_BOOST-Pad27)") (class "Default")
      (node (ref "U2") (pin "27") (pinfunction "PA_BOOST_27") (pintype "output"))
    )
    (net (code "72") (name "unconnected-(U3-NC1-Pad1)") (class "Default")
      (node (ref "U3") (pin "1") (pinfunction "NC1_1") (pintype "bidirectional"))
    )
    (net (code "73") (name "unconnected-(U3-NC2-Pad2)") (class "Default")
      (node (ref "U3") (pin "2") (pinfunction "NC2_2") (pintype "bidirectional"))
    )
    (net (code "74") (name "unconnected-(U3-NC3-Pad3)") (class "Default")
      (node (ref "U3") (pin "3") (pinfunction "NC3_3") (pintype "bidirectional"))
    )
    (net (code "75") (name "unconnected-(U3-NC7-Pad7)") (class "Default")
      (node (ref "U3") (pin "7") (pinfunction "NC7_7") (pintype "bidirectional"))
    )
  )
)
